# BH_Pzem_WI_FI_SHIELD.net
KiCad netlist of a schematic drawn in EAGLE
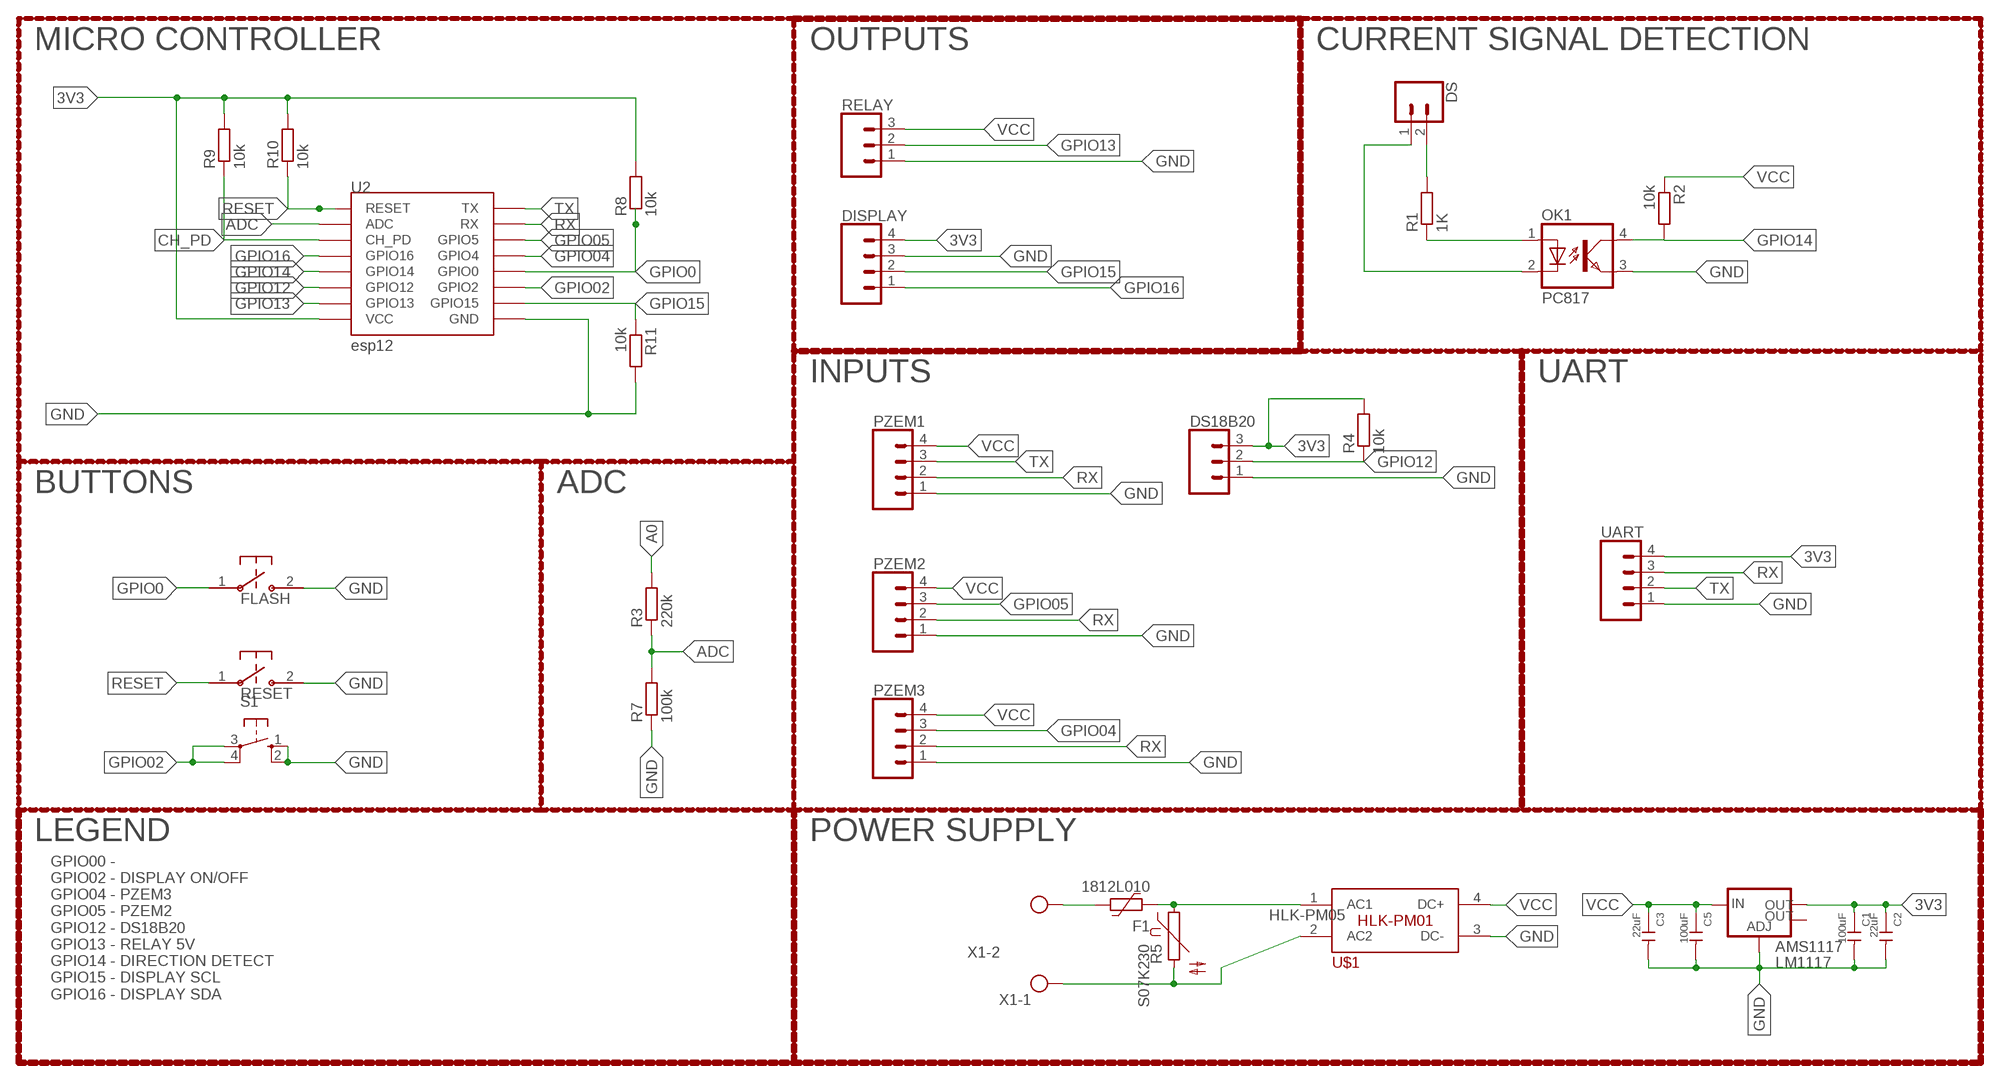
[diagram p0: schematic, sheet 1]

(export (version "E")
  (design (tool "Eeschema 10.0.6"))
  (components
    (comp (ref "AMS1117")
      (value "LM1117")
      (footprint "eagle-import:SOT223")
      (libsource (lib "eagle-import") (part "V_REG_LM1117SOT223"))
    )
    (comp (ref "C1")
      (value "100uF")
      (footprint "eagle-import:C1206")
      (fields (field (name "MPN") "CC1206KKX7RCBB102"))
      (libsource (lib "eagle-import") (part "CERAMIC-1NF-1KV-10%-X7R?(1206)"))
    )
    (comp (ref "C2")
      (value "22uF")
      (footprint "eagle-import:C1206")
      (fields (field (name "MPN") "CC1206KKX7RCBB102"))
      (libsource (lib "eagle-import") (part "CERAMIC-1NF-1KV-10%-X7R?(1206)"))
    )
    (comp (ref "C3")
      (value "22uF")
      (footprint "eagle-import:C1206")
      (fields (field (name "MPN") "CC1206KKX7RCBB102"))
      (libsource (lib "eagle-import") (part "CERAMIC-1NF-1KV-10%-X7R?(1206)"))
    )
    (comp (ref "C5")
      (value "100uF")
      (footprint "eagle-import:C1206")
      (fields (field (name "MPN") "CC1206KKX7RCBB102"))
      (libsource (lib "eagle-import") (part "CERAMIC-1NF-1KV-10%-X7R?(1206)"))
    )
    (comp (ref "DISPLAY")
      (value "CONN_04JST-PTH-VERT")
      (footprint "eagle-import:JST-4-PTH-VERT")
      (libsource (lib "eagle-import") (part "CONN_04JST-PTH-VERT"))
    )
    (comp (ref "DS")
      (value "CONN_02")
      (footprint "eagle-import:1X02")
      (libsource (lib "eagle-import") (part "CONN_02"))
    )
    (comp (ref "DS18B20")
      (value "CONN_03JST-PTH-VERT")
      (footprint "eagle-import:JST-3-PTH-VERT")
      (libsource (lib "eagle-import") (part "CONN_03JST-PTH-VERT"))
    )
    (comp (ref "F1")
      (value "1812L010")
      (footprint "eagle-import:1812L")
      (fields (field (name "MF") "Littelfuse"))
      (libsource (lib "eagle-import") (part "?1812L010"))
    )
    (comp (ref "FLASH")
      (value "B3U-1000P-2P-SMD")
      (footprint "eagle-import:B3U-1000P")
      (fields
        (field (name "MANUFACTURER") "Omron")
        (field (name "MPN") "B3U-1000P")
        (field (name "SPICEPREFIX") "F")
      )
      (libsource (lib "eagle-import") (part "B3U-1000P"))
    )
    (comp (ref "OK1")
      (value "PC817")
      (footprint "eagle-import:DIL04")
      (fields (field (name "MPN") "PC817X4J000F"))
      (libsource (lib "eagle-import") (part "PC817"))
    )
    (comp (ref "PZEM1")
      (value "CONN_04JST-PTH-VERT")
      (footprint "eagle-import:JST-4-PTH-VERT")
      (libsource (lib "eagle-import") (part "CONN_04JST-PTH-VERT"))
    )
    (comp (ref "PZEM2")
      (value "CONN_04JST-PTH-VERT")
      (footprint "eagle-import:JST-4-PTH-VERT")
      (libsource (lib "eagle-import") (part "CONN_04JST-PTH-VERT"))
    )
    (comp (ref "PZEM3")
      (value "CONN_04JST-PTH-VERT")
      (footprint "eagle-import:JST-4-PTH-VERT")
      (libsource (lib "eagle-import") (part "CONN_04JST-PTH-VERT"))
    )
    (comp (ref "R1")
      (value "1K")
      (footprint "eagle-import:R0603")
      (libsource (lib "eagle-import") (part "R-EU_R0603"))
    )
    (comp (ref "R2")
      (value "10k")
      (footprint "eagle-import:R0603")
      (libsource (lib "eagle-import") (part "R-EU_R0603"))
    )
    (comp (ref "R3")
      (value "220k")
      (footprint "eagle-import:R0603")
      (libsource (lib "eagle-import") (part "R-EU_R0603"))
    )
    (comp (ref "R4")
      (value "10k")
      (footprint "eagle-import:R0603")
      (libsource (lib "eagle-import") (part "R-EU_R0603"))
    )
    (comp (ref "R5")
      (value "S07K230")
      (footprint "eagle-import:S07K230")
      (libsource (lib "eagle-import") (part "S07K230"))
    )
    (comp (ref "R7")
      (value "100k")
      (footprint "eagle-import:R0603")
      (libsource (lib "eagle-import") (part "R-EU_R0603"))
    )
    (comp (ref "R8")
      (value "10k")
      (footprint "eagle-import:R0603")
      (libsource (lib "eagle-import") (part "R-EU_R0603"))
    )
    (comp (ref "R9")
      (value "10k")
      (footprint "eagle-import:R0603")
      (libsource (lib "eagle-import") (part "R-EU_R0603"))
    )
    (comp (ref "R10")
      (value "10k")
      (footprint "eagle-import:R0603")
      (libsource (lib "eagle-import") (part "R-EU_R0603"))
    )
    (comp (ref "R11")
      (value "10k")
      (footprint "eagle-import:R0603")
      (libsource (lib "eagle-import") (part "R-EU_R0603"))
    )
    (comp (ref "RELAY")
      (value "CONN_03JST-PTH-VERT")
      (footprint "eagle-import:JST-3-PTH-VERT")
      (libsource (lib "eagle-import") (part "CONN_03JST-PTH-VERT"))
    )
    (comp (ref "RESET")
      (value "B3U-1000P-2P-SMD")
      (footprint "eagle-import:B3U-1000P")
      (fields (field (name "MANUFACTURER") "Omron") (field (name "MPN") "B3U-1000P"))
      (libsource (lib "eagle-import") (part "B3U-1000P"))
    )
    (comp (ref "S1")
      (value "10-XX")
      (footprint "eagle-import:B3F-10XX")
      (fields (field (name "MPN") "B3F-1000"))
      (libsource (lib "eagle-import") (part "10-XX"))
    )
    (comp (ref "U$1")
      (value "HLK-PM01")
      (footprint "eagle-import:HLK-PM01")
      (fields (field (name "MF") "Hi-link") (field (name "MP") "hlk-pm01"))
      (libsource (lib "eagle-import") (part "HLK-PM01"))
    )
    (comp (ref "U2")
      (value "esp12")
      (footprint "eagle-import:ESP12-SMD")
      (libsource (lib "eagle-import") (part "ESP12SMD"))
    )
    (comp (ref "UART")
      (value "CONN_04JST-PTH-VERT")
      (footprint "eagle-import:JST-4-PTH-VERT")
      (libsource (lib "eagle-import") (part "CONN_04JST-PTH-VERT"))
    )
    (comp (ref "X1")
      (value "W237-102")
      (footprint "eagle-import:W237-102")
      (fields (field (name "MPN") "237-102"))
      (libsource (lib "eagle-import") (part "W237-102"))
    )
  )
  (nets
    (net (code "1") (name "3V3") (class "Default")
      (node (ref "AMS1117") (pin "2") (pinfunction "OUT_2") (pintype "output"))
      (node (ref "C1") (pin "1") (pinfunction "1_1") (pintype "passive"))
      (node (ref "C2") (pin "1") (pinfunction "1_1") (pintype "passive"))
      (node (ref "DISPLAY") (pin "4") (pinfunction "4_4") (pintype "passive"))
      (node (ref "DS18B20") (pin "3") (pinfunction "3_3") (pintype "passive"))
      (node (ref "R10") (pin "2") (pinfunction "2_2") (pintype "passive"))
      (node (ref "R4") (pin "2") (pinfunction "2_2") (pintype "passive"))
      (node (ref "R8") (pin "2") (pinfunction "2_2") (pintype "passive"))
      (node (ref "R9") (pin "2") (pinfunction "2_2") (pintype "passive"))
      (node (ref "U2") (pin "VCC") (pinfunction "VCC_VCC") (pintype "bidirectional"))
      (node (ref "UART") (pin "4") (pinfunction "4_4") (pintype "passive"))
    )
    (net (code "2") (name "A0") (class "Default")
      (node (ref "R3") (pin "2") (pinfunction "2_2") (pintype "passive"))
    )
    (net (code "3") (name "ADC") (class "Default")
      (node (ref "R3") (pin "1") (pinfunction "1_1") (pintype "passive"))
      (node (ref "R7") (pin "2") (pinfunction "2_2") (pintype "passive"))
      (node (ref "U2") (pin "ADC") (pinfunction "ADC_ADC") (pintype "bidirectional"))
    )
    (net (code "4") (name "CH_PD") (class "Default")
      (node (ref "R9") (pin "1") (pinfunction "1_1") (pintype "passive"))
      (node (ref "U2") (pin "CH_PD") (pinfunction "CH_PD_CH_PD") (pintype "bidirectional"))
    )
    (net (code "5") (name "GND") (class "Default")
      (node (ref "AMS1117") (pin "1") (pinfunction "ADJ_1") (pintype "input"))
      (node (ref "C1") (pin "2") (pinfunction "2_2") (pintype "passive"))
      (node (ref "C2") (pin "2") (pinfunction "2_2") (pintype "passive"))
      (node (ref "C3") (pin "2") (pinfunction "2_2") (pintype "passive"))
      (node (ref "C5") (pin "2") (pinfunction "2_2") (pintype "passive"))
      (node (ref "DISPLAY") (pin "3") (pinfunction "3_3") (pintype "passive"))
      (node (ref "DS18B20") (pin "1") (pinfunction "1_1") (pintype "passive"))
      (node (ref "FLASH") (pin "2") (pinfunction "P$2_2") (pintype "passive"))
      (node (ref "OK1") (pin "3") (pinfunction "EMIT_3") (pintype "passive"))
      (node (ref "PZEM1") (pin "1") (pinfunction "1_1") (pintype "passive"))
      (node (ref "PZEM2") (pin "1") (pinfunction "1_1") (pintype "passive"))
      (node (ref "PZEM3") (pin "1") (pinfunction "1_1") (pintype "passive"))
      (node (ref "R11") (pin "2") (pinfunction "2_2") (pintype "passive"))
      (node (ref "R7") (pin "1") (pinfunction "1_1") (pintype "passive"))
      (node (ref "RELAY") (pin "1") (pinfunction "1_1") (pintype "passive"))
      (node (ref "RESET") (pin "2") (pinfunction "P$2_2") (pintype "passive"))
      (node (ref "S1") (pin "1") (pinfunction "S_1") (pintype "passive"))
      (node (ref "S1") (pin "2") (pinfunction "S1_2") (pintype "passive"))
      (node (ref "U$1") (pin "3") (pinfunction "DC-_3") (pintype "power_in"))
      (node (ref "U2") (pin "GND") (pinfunction "GND_GND") (pintype "bidirectional"))
      (node (ref "UART") (pin "1") (pinfunction "1_1") (pintype "passive"))
    )
    (net (code "6") (name "GPIO0") (class "Default")
      (node (ref "FLASH") (pin "1") (pinfunction "P$1_1") (pintype "passive"))
      (node (ref "R8") (pin "1") (pinfunction "1_1") (pintype "passive"))
      (node (ref "U2") (pin "GPIO0") (pinfunction "GPIO0_GPIO0") (pintype "bidirectional"))
    )
    (net (code "7") (name "GPIO02") (class "Default")
      (node (ref "S1") (pin "3") (pinfunction "P_3") (pintype "passive"))
      (node (ref "S1") (pin "4") (pinfunction "P1_4") (pintype "passive"))
      (node (ref "U2") (pin "GPIO2") (pinfunction "GPIO2_GPIO2") (pintype "bidirectional"))
    )
    (net (code "8") (name "GPIO04") (class "Default")
      (node (ref "PZEM3") (pin "3") (pinfunction "3_3") (pintype "passive"))
      (node (ref "U2") (pin "GPIO4") (pinfunction "GPIO4_GPIO4") (pintype "bidirectional"))
    )
    (net (code "9") (name "GPIO05") (class "Default")
      (node (ref "PZEM2") (pin "3") (pinfunction "3_3") (pintype "passive"))
      (node (ref "U2") (pin "GPIO5") (pinfunction "GPIO5_GPIO5") (pintype "bidirectional"))
    )
    (net (code "10") (name "GPIO12") (class "Default")
      (node (ref "DS18B20") (pin "2") (pinfunction "2_2") (pintype "passive"))
      (node (ref "R4") (pin "1") (pinfunction "1_1") (pintype "passive"))
      (node (ref "U2") (pin "GPIO12") (pinfunction "GPIO12_GPIO12") (pintype "bidirectional"))
    )
    (net (code "11") (name "GPIO13") (class "Default")
      (node (ref "RELAY") (pin "2") (pinfunction "2_2") (pintype "passive"))
      (node (ref "U2") (pin "GPIO13") (pinfunction "GPIO13_GPIO13") (pintype "bidirectional"))
    )
    (net (code "12") (name "GPIO14") (class "Default")
      (node (ref "OK1") (pin "4") (pinfunction "COL_4") (pintype "passive"))
      (node (ref "R2") (pin "2") (pinfunction "2_2") (pintype "passive"))
      (node (ref "U2") (pin "GPIO14") (pinfunction "GPIO14_GPIO14") (pintype "bidirectional"))
    )
    (net (code "13") (name "GPIO15") (class "Default")
      (node (ref "DISPLAY") (pin "2") (pinfunction "2_2") (pintype "passive"))
      (node (ref "R11") (pin "1") (pinfunction "1_1") (pintype "passive"))
      (node (ref "U2") (pin "GPIO15") (pinfunction "GPIO15_GPIO15") (pintype "bidirectional"))
    )
    (net (code "14") (name "GPIO16") (class "Default")
      (node (ref "DISPLAY") (pin "1") (pinfunction "1_1") (pintype "passive"))
      (node (ref "U2") (pin "GPIO16") (pinfunction "GPIO16_GPIO16") (pintype "bidirectional"))
    )
    (net (code "15") (name "Net-(DS-Pad2)") (class "Default")
      (node (ref "DS") (pin "2") (pinfunction "2_2") (pintype "passive"))
      (node (ref "R1") (pin "2") (pinfunction "2_2") (pintype "passive"))
    )
    (net (code "16") (name "Net-(OK1-A)") (class "Default")
      (node (ref "OK1") (pin "1") (pinfunction "A_1") (pintype "passive"))
      (node (ref "R1") (pin "1") (pinfunction "1_1") (pintype "passive"))
    )
    (net (code "17") (name "Net-(OK1-C)") (class "Default")
      (node (ref "DS") (pin "1") (pinfunction "1_1") (pintype "passive"))
      (node (ref "OK1") (pin "2") (pinfunction "C_2") (pintype "passive"))
    )
    (net (code "18") (name "Net-(U$1-AC1)") (class "Default")
      (node (ref "F1") (pin "2") (pinfunction "2_2") (pintype "passive"))
      (node (ref "R5") (pin "1") (pinfunction "1_1") (pintype "passive"))
      (node (ref "U$1") (pin "1") (pinfunction "AC1_1") (pintype "power_in"))
    )
    (net (code "19") (name "Net-(U$1-AC2)") (class "Default")
      (node (ref "R5") (pin "2") (pinfunction "2_2") (pintype "passive"))
      (node (ref "U$1") (pin "2") (pinfunction "AC2_2") (pintype "power_in"))
      (node (ref "X1") (pin "1") (pinfunction "KL_1") (pintype "passive"))
    )
    (net (code "20") (name "Net-(X1B-KL)") (class "Default")
      (node (ref "F1") (pin "1") (pinfunction "1_1") (pintype "passive"))
      (node (ref "X1") (pin "2") (pinfunction "KL_2") (pintype "passive"))
    )
    (net (code "21") (name "RESET") (class "Default")
      (node (ref "R10") (pin "1") (pinfunction "1_1") (pintype "passive"))
      (node (ref "RESET") (pin "1") (pinfunction "P$1_1") (pintype "passive"))
      (node (ref "U2") (pin "RESET") (pinfunction "RESET_RESET") (pintype "bidirectional"))
    )
    (net (code "22") (name "RX") (class "Default")
      (node (ref "PZEM1") (pin "2") (pinfunction "2_2") (pintype "passive"))
      (node (ref "PZEM2") (pin "2") (pinfunction "2_2") (pintype "passive"))
      (node (ref "PZEM3") (pin "2") (pinfunction "2_2") (pintype "passive"))
      (node (ref "U2") (pin "RXD0") (pinfunction "RX_RXD0") (pintype "bidirectional"))
      (node (ref "UART") (pin "3") (pinfunction "3_3") (pintype "passive"))
    )
    (net (code "23") (name "TX") (class "Default")
      (node (ref "PZEM1") (pin "3") (pinfunction "3_3") (pintype "passive"))
      (node (ref "U2") (pin "TXD0") (pinfunction "TX_TXD0") (pintype "bidirectional"))
      (node (ref "UART") (pin "2") (pinfunction "2_2") (pintype "passive"))
    )
    (net (code "24") (name "VCC") (class "Default")
      (node (ref "AMS1117") (pin "3") (pinfunction "IN_3") (pintype "input"))
      (node (ref "C3") (pin "1") (pinfunction "1_1") (pintype "passive"))
      (node (ref "C5") (pin "1") (pinfunction "1_1") (pintype "passive"))
      (node (ref "PZEM1") (pin "4") (pinfunction "4_4") (pintype "passive"))
      (node (ref "PZEM2") (pin "4") (pinfunction "4_4") (pintype "passive"))
      (node (ref "PZEM3") (pin "4") (pinfunction "4_4") (pintype "passive"))
      (node (ref "R2") (pin "1") (pinfunction "1_1") (pintype "passive"))
      (node (ref "RELAY") (pin "3") (pinfunction "3_3") (pintype "passive"))
      (node (ref "U$1") (pin "4") (pinfunction "DC+_4") (pintype "power_in"))
    )
    (net (code "25") (name "unconnected-(AMS1117-OUT-Pad4)") (class "Default")
      (node (ref "AMS1117") (pin "4") (pinfunction "OUT_4") (pintype "output"))
    )
  )
)
